# RGB_i2c_LED.net
KiCad netlist of a schematic drawn in EAGLE
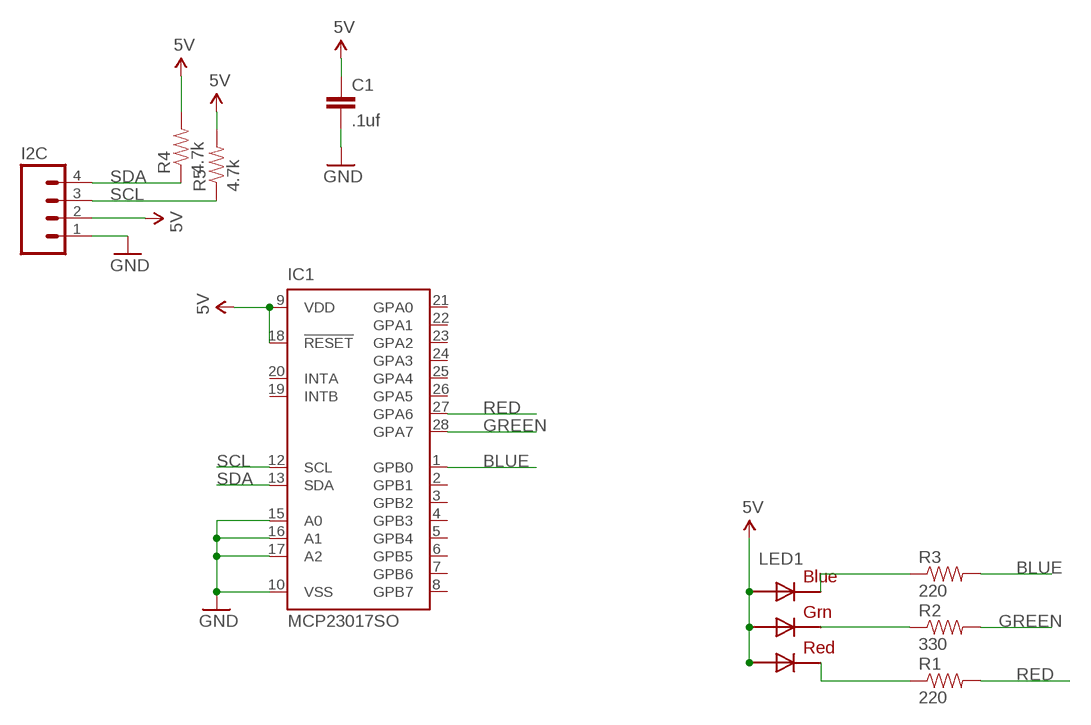
[diagram p0: schematic, sheet 1]

(export (version "E")
  (design (tool "Eeschema 10.0.6"))
  (components
    (comp (ref "C1")
      (value ".1uf")
      (footprint "eagle-import:0805")
      (libsource (lib "eagle-import") (part "CAP0805"))
    )
    (comp (ref "I2C")
      (value "M04LOCK")
      (footprint "eagle-import:1X04_LOCK")
      (libsource (lib "eagle-import") (part "M04LOCK"))
    )
    (comp (ref "IC1")
      (value "MCP23017SO")
      (footprint "eagle-import:SO28W")
      (libsource (lib "eagle-import") (part "MCP23017SO"))
    )
    (comp (ref "LED1")
      (value "RGBLED5050")
      (footprint "eagle-import:RGBLED5050")
      (libsource (lib "eagle-import") (part "RGBLED5050"))
    )
    (comp (ref "R1")
      (value "220")
      (footprint "eagle-import:0805")
      (libsource (lib "eagle-import") (part "RESISTOR0805-RES"))
    )
    (comp (ref "R2")
      (value "330")
      (footprint "eagle-import:0805")
      (libsource (lib "eagle-import") (part "RESISTOR0805-RES"))
    )
    (comp (ref "R3")
      (value "220")
      (footprint "eagle-import:0805")
      (libsource (lib "eagle-import") (part "RESISTOR0805-RES"))
    )
    (comp (ref "R4")
      (value "4.7k")
      (footprint "eagle-import:0805")
      (libsource (lib "eagle-import") (part "RESISTOR0805-RES"))
    )
    (comp (ref "R5")
      (value "4.7k")
      (footprint "eagle-import:0805")
      (libsource (lib "eagle-import") (part "RESISTOR0805-RES"))
    )
  )
  (nets
    (net (code "1") (name "/BLUE") (class "Default")
      (node (ref "IC1") (pin "1") (pinfunction "GPB0_1") (pintype "bidirectional"))
      (node (ref "R3") (pin "2") (pinfunction "2_2") (pintype "passive"))
    )
    (net (code "2") (name "/GREEN") (class "Default")
      (node (ref "IC1") (pin "28") (pinfunction "GPA7_28") (pintype "bidirectional"))
      (node (ref "R2") (pin "2") (pinfunction "2_2") (pintype "passive"))
    )
    (net (code "3") (name "/RED") (class "Default")
      (node (ref "IC1") (pin "27") (pinfunction "GPA6_27") (pintype "bidirectional"))
      (node (ref "R1") (pin "2") (pinfunction "2_2") (pintype "passive"))
    )
    (net (code "4") (name "/SCL") (class "Default")
      (node (ref "I2C") (pin "3") (pinfunction "3_3") (pintype "passive"))
      (node (ref "IC1") (pin "12") (pinfunction "SCL_12") (pintype "input"))
      (node (ref "R5") (pin "1") (pinfunction "1_1") (pintype "passive"))
    )
    (net (code "5") (name "/SDA") (class "Default")
      (node (ref "I2C") (pin "4") (pinfunction "4_4") (pintype "passive"))
      (node (ref "IC1") (pin "13") (pinfunction "SDA_13") (pintype "bidirectional"))
      (node (ref "R4") (pin "1") (pinfunction "1_1") (pintype "passive"))
    )
    (net (code "6") (name "5V") (class "Default")
      (node (ref "C1") (pin "1") (pinfunction "1_1") (pintype "passive"))
      (node (ref "I2C") (pin "2") (pinfunction "2_2") (pintype "passive"))
      (node (ref "IC1") (pin "18") (pinfunction "~{RESET}_18") (pintype "input"))
      (node (ref "IC1") (pin "9") (pinfunction "VDD_9") (pintype "power_in"))
      (node (ref "LED1") (pin "4") (pinfunction "GREEN_A_4") (pintype "bidirectional"))
      (node (ref "LED1") (pin "5") (pinfunction "RED_A_5") (pintype "bidirectional"))
      (node (ref "LED1") (pin "6") (pinfunction "BLUE_A_6") (pintype "bidirectional"))
      (node (ref "R4") (pin "2") (pinfunction "2_2") (pintype "passive"))
      (node (ref "R5") (pin "2") (pinfunction "2_2") (pintype "passive"))
    )
    (net (code "7") (name "GND") (class "Default")
      (node (ref "C1") (pin "2") (pinfunction "2_2") (pintype "passive"))
      (node (ref "I2C") (pin "1") (pinfunction "1_1") (pintype "passive"))
      (node (ref "IC1") (pin "10") (pinfunction "VSS_10") (pintype "power_in"))
      (node (ref "IC1") (pin "15") (pinfunction "A0_15") (pintype "input"))
      (node (ref "IC1") (pin "16") (pinfunction "A1_16") (pintype "input"))
      (node (ref "IC1") (pin "17") (pinfunction "A2_17") (pintype "input"))
    )
    (net (code "8") (name "Net-(LED1-BLUE_C)") (class "Default")
      (node (ref "LED1") (pin "3") (pinfunction "BLUE_C_3") (pintype "bidirectional"))
      (node (ref "R3") (pin "1") (pinfunction "1_1") (pintype "passive"))
    )
    (net (code "9") (name "Net-(LED1-GREEN_C)") (class "Default")
      (node (ref "LED1") (pin "1") (pinfunction "GREEN_C_1") (pintype "bidirectional"))
      (node (ref "R2") (pin "1") (pinfunction "1_1") (pintype "passive"))
    )
    (net (code "10") (name "Net-(LED1-RED_C)") (class "Default")
      (node (ref "LED1") (pin "2") (pinfunction "RED_C_2") (pintype "bidirectional"))
      (node (ref "R1") (pin "1") (pinfunction "1_1") (pintype "passive"))
    )
    (net (code "11") (name "unconnected-(IC1-GPA0-Pad21)") (class "Default")
      (node (ref "IC1") (pin "21") (pinfunction "GPA0_21") (pintype "bidirectional"))
    )
    (net (code "12") (name "unconnected-(IC1-GPA1-Pad22)") (class "Default")
      (node (ref "IC1") (pin "22") (pinfunction "GPA1_22") (pintype "bidirectional"))
    )
    (net (code "13") (name "unconnected-(IC1-GPA2-Pad23)") (class "Default")
      (node (ref "IC1") (pin "23") (pinfunction "GPA2_23") (pintype "bidirectional"))
    )
    (net (code "14") (name "unconnected-(IC1-GPA3-Pad24)") (class "Default")
      (node (ref "IC1") (pin "24") (pinfunction "GPA3_24") (pintype "bidirectional"))
    )
    (net (code "15") (name "unconnected-(IC1-GPA4-Pad25)") (class "Default")
      (node (ref "IC1") (pin "25") (pinfunction "GPA4_25") (pintype "bidirectional"))
    )
    (net (code "16") (name "unconnected-(IC1-GPA5-Pad26)") (class "Default")
      (node (ref "IC1") (pin "26") (pinfunction "GPA5_26") (pintype "bidirectional"))
    )
    (net (code "17") (name "unconnected-(IC1-GPB1-Pad2)") (class "Default")
      (node (ref "IC1") (pin "2") (pinfunction "GPB1_2") (pintype "bidirectional"))
    )
    (net (code "18") (name "unconnected-(IC1-GPB2-Pad3)") (class "Default")
      (node (ref "IC1") (pin "3") (pinfunction "GPB2_3") (pintype "bidirectional"))
    )
    (net (code "19") (name "unconnected-(IC1-GPB3-Pad4)") (class "Default")
      (node (ref "IC1") (pin "4") (pinfunction "GPB3_4") (pintype "bidirectional"))
    )
    (net (code "20") (name "unconnected-(IC1-GPB4-Pad5)") (class "Default")
      (node (ref "IC1") (pin "5") (pinfunction "GPB4_5") (pintype "bidirectional"))
    )
    (net (code "21") (name "unconnected-(IC1-GPB5-Pad6)") (class "Default")
      (node (ref "IC1") (pin "6") (pinfunction "GPB5_6") (pintype "bidirectional"))
    )
    (net (code "22") (name "unconnected-(IC1-GPB6-Pad7)") (class "Default")
      (node (ref "IC1") (pin "7") (pinfunction "GPB6_7") (pintype "bidirectional"))
    )
    (net (code "23") (name "unconnected-(IC1-GPB7-Pad8)") (class "Default")
      (node (ref "IC1") (pin "8") (pinfunction "GPB7_8") (pintype "bidirectional"))
    )
    (net (code "24") (name "unconnected-(IC1-INTA-Pad20)") (class "Default")
      (node (ref "IC1") (pin "20") (pinfunction "INTA_20") (pintype "output"))
    )
    (net (code "25") (name "unconnected-(IC1-INTB-Pad19)") (class "Default")
      (node (ref "IC1") (pin "19") (pinfunction "INTB_19") (pintype "output"))
    )
  )
)
